# norbi_lm_main.net
KiCad netlist of a schematic drawn in Altium Designer
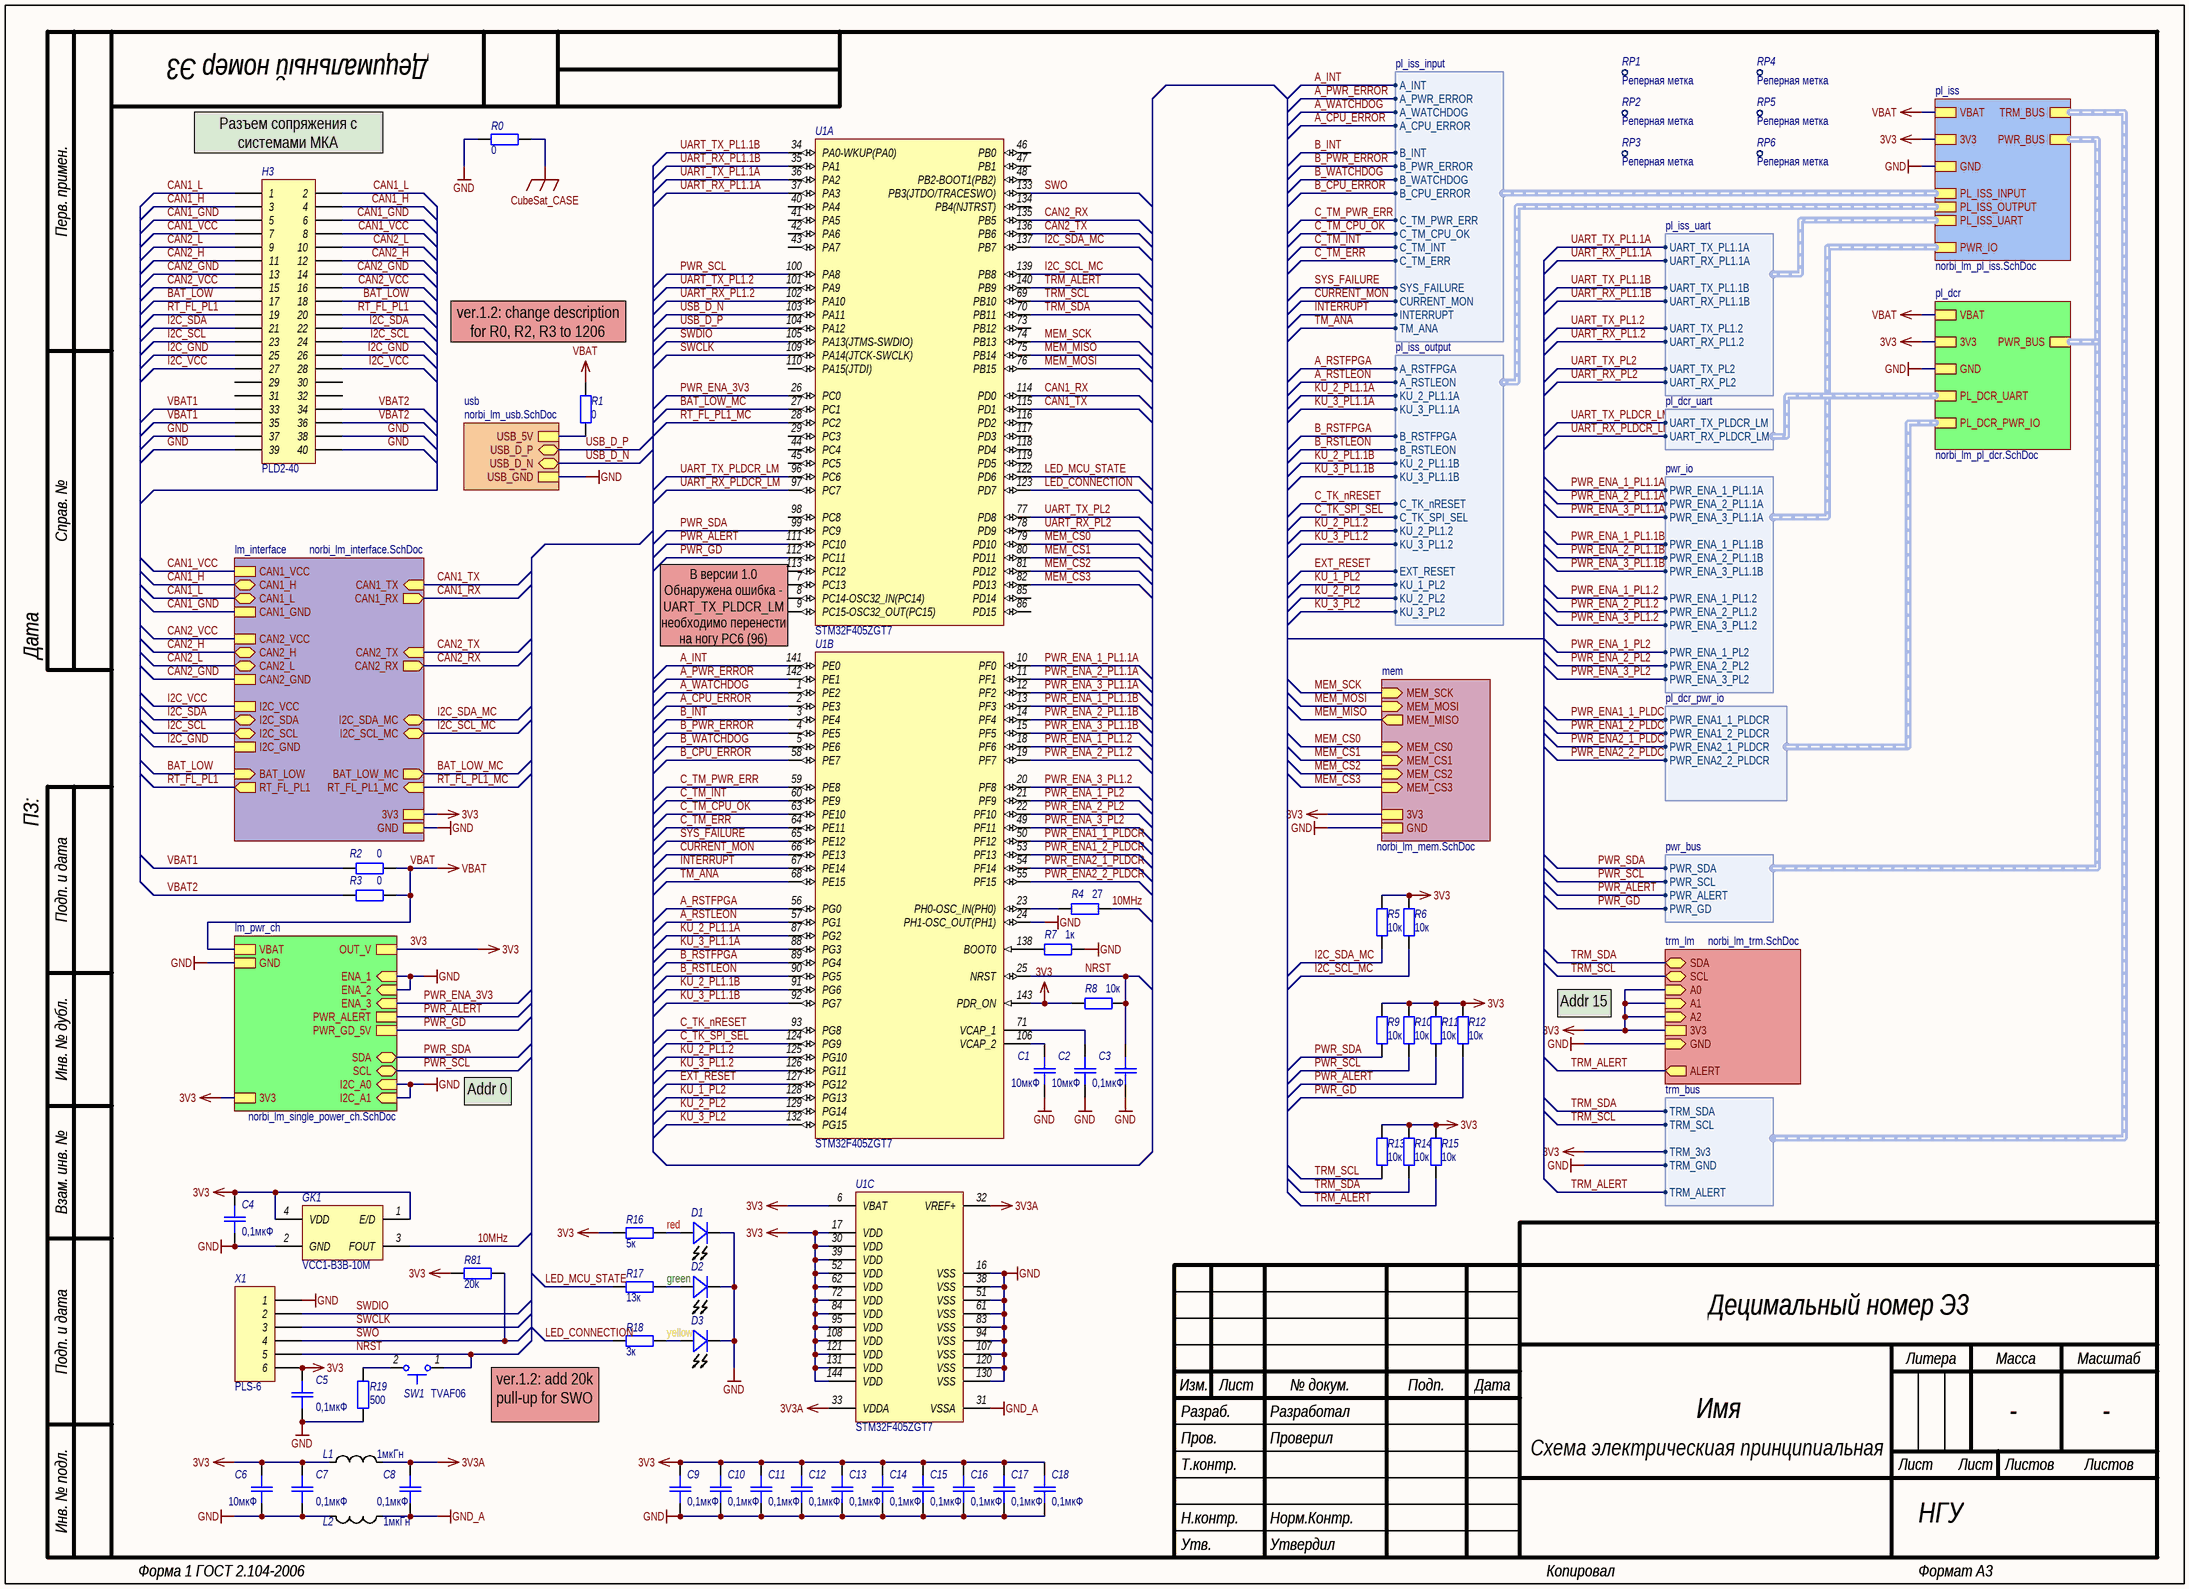
[diagram p0: norbi_lm_main.SchDoc]

(export (version "E")
  (design (tool "Eeschema 10.0.6"))
  (components
    (comp (ref "C1")
      (value "10мкФ")
      (footprint "CR-0603")
      (description "Конденсатор для поверхностного монтажа")
      (libsource (lib "my_passive") (part "C_smd"))
    )
    (comp (ref "C2")
      (value "10мкФ")
      (footprint "CR-0603")
      (description "Конденсатор для поверхностного монтажа")
      (libsource (lib "my_passive") (part "C_smd"))
    )
    (comp (ref "C3")
      (value "0,1мкФ")
      (footprint "CR-0603")
      (description "Конденсатор для поверхностного монтажа")
      (libsource (lib "my_passive") (part "C_smd"))
    )
    (comp (ref "C4")
      (value "0,1мкФ")
      (footprint "CR-0603")
      (description "Конденсатор для поверхностного монтажа")
      (libsource (lib "my_passive") (part "C_smd"))
    )
    (comp (ref "C5")
      (value "0,1мкФ")
      (footprint "CR-0603")
      (description "Конденсатор для поверхностного монтажа")
      (libsource (lib "my_passive") (part "C_smd"))
    )
    (comp (ref "C6")
      (value "10мкФ")
      (footprint "CR-0603")
      (description "Конденсатор для поверхностного монтажа")
      (libsource (lib "my_passive") (part "C_smd"))
    )
    (comp (ref "C7")
      (value "0,1мкФ")
      (footprint "CR-0603")
      (description "Конденсатор для поверхностного монтажа")
      (libsource (lib "my_passive") (part "C_smd"))
    )
    (comp (ref "C8")
      (value "0,1мкФ")
      (footprint "CR-0603")
      (description "Конденсатор для поверхностного монтажа")
      (libsource (lib "my_passive") (part "C_smd"))
    )
    (comp (ref "C9")
      (value "0,1мкФ")
      (footprint "CR-0603")
      (description "Конденсатор для поверхностного монтажа")
      (libsource (lib "my_passive") (part "C_smd"))
    )
    (comp (ref "C10")
      (value "0,1мкФ")
      (footprint "CR-0603")
      (description "Конденсатор для поверхностного монтажа")
      (libsource (lib "my_passive") (part "C_smd"))
    )
    (comp (ref "C11")
      (value "0,1мкФ")
      (footprint "CR-0603")
      (description "Конденсатор для поверхностного монтажа")
      (libsource (lib "my_passive") (part "C_smd"))
    )
    (comp (ref "C12")
      (value "0,1мкФ")
      (footprint "CR-0603")
      (description "Конденсатор для поверхностного монтажа")
      (libsource (lib "my_passive") (part "C_smd"))
    )
    (comp (ref "C13")
      (value "0,1мкФ")
      (footprint "CR-0603")
      (description "Конденсатор для поверхностного монтажа")
      (libsource (lib "my_passive") (part "C_smd"))
    )
    (comp (ref "C14")
      (value "0,1мкФ")
      (footprint "CR-0603")
      (description "Конденсатор для поверхностного монтажа")
      (libsource (lib "my_passive") (part "C_smd"))
    )
    (comp (ref "C15")
      (value "0,1мкФ")
      (footprint "CR-0603")
      (description "Конденсатор для поверхностного монтажа")
      (libsource (lib "my_passive") (part "C_smd"))
    )
    (comp (ref "C16")
      (value "0,1мкФ")
      (footprint "CR-0603")
      (description "Конденсатор для поверхностного монтажа")
      (libsource (lib "my_passive") (part "C_smd"))
    )
    (comp (ref "C17")
      (value "0,1мкФ")
      (footprint "CR-0603")
      (description "Конденсатор для поверхностного монтажа")
      (libsource (lib "my_passive") (part "C_smd"))
    )
    (comp (ref "C18")
      (value "0,1мкФ")
      (footprint "CR-0603")
      (description "Конденсатор для поверхностного монтажа")
      (libsource (lib "my_passive") (part "C_smd"))
    )
    (comp (ref "D1")
      (value "red")
      (footprint "LED-0805")
      (fields (field (name "Comment") "LED"))
      (libsource (lib "my_semicond") (part "LED"))
    )
    (comp (ref "D2")
      (value "green")
      (footprint "LED-0805")
      (fields (field (name "Comment") "LED"))
      (libsource (lib "my_semicond") (part "LED"))
    )
    (comp (ref "D3")
      (value "yellow")
      (footprint "LED-0805")
      (fields (field (name "Comment") "LED"))
      (libsource (lib "my_semicond") (part "LED"))
    )
    (comp (ref "GK1")
      (value "VCC1")
      (footprint "5x7 Crystall Oscillatior")
      (fields (field (name "НАИМЕНОВАНИЕ") "VCC1-B3B-10M"))
      (libsource (lib "my_integrated_circuit") (part "Crystall Oscillator"))
    )
    (comp (ref "H3")
      (value "Header 20X2H")
      (footprint "PLD2-40 (DS-1025-05 2x20)")
      (description "Header, 20-Pin, Dual row, Right Angle")
      (fields (field (name "НАИМЕНОВАНИЕ") "PLD2-40"))
      (libsource (lib "my_connector") (part "HDR2X20"))
    )
    (comp (ref "L1")
      (value "1мкГн")
      (footprint "CR-0805")
      (description "Индуктивность для поверхностнгого монтажа")
      (libsource (lib "my_passive") (part "L_smd"))
    )
    (comp (ref "L2")
      (value "1мкГн")
      (footprint "CR-0805")
      (description "Индуктивность для поверхностнгого монтажа")
      (libsource (lib "my_passive") (part "L_smd"))
    )
    (comp (ref "R0")
      (value "0")
      (footprint "CR-0805")
      (description "Резистор для поверхностного монтажа")
      (libsource (lib "") (part "R_smd_3"))
    )
    (comp (ref "R1")
      (value "0")
      (footprint "CR-1206")
      (description "Резистор для поверхностного монтажа")
      (libsource (lib "") (part "R_smd_2"))
    )
    (comp (ref "R2")
      (value "0")
      (footprint "CR-1206")
      (description "Резистор для поверхностного монтажа")
      (libsource (lib "my_passive") (part "R_smd"))
    )
    (comp (ref "R3")
      (value "0")
      (footprint "CR-1206")
      (description "Резистор для поверхностного монтажа")
      (libsource (lib "my_passive") (part "R_smd"))
    )
    (comp (ref "R4")
      (value "27")
      (footprint "CR-0603")
      (description "Резистор для поверхностного монтажа")
      (libsource (lib "my_passive") (part "R_smd"))
    )
    (comp (ref "R5")
      (value "10к")
      (footprint "CR-0603")
      (description "Резистор для поверхностного монтажа")
      (libsource (lib "") (part "R_smd_1"))
    )
    (comp (ref "R6")
      (value "10к")
      (footprint "CR-0603")
      (description "Резистор для поверхностного монтажа")
      (libsource (lib "") (part "R_smd_1"))
    )
    (comp (ref "R7")
      (value "1к")
      (footprint "CR-0603")
      (description "Резистор для поверхностного монтажа")
      (libsource (lib "") (part "R_smd_3"))
    )
    (comp (ref "R8")
      (value "10к")
      (footprint "CR-0603")
      (description "Резистор для поверхностного монтажа")
      (libsource (lib "") (part "R_smd_3"))
    )
    (comp (ref "R9")
      (value "10к")
      (footprint "CR-0603")
      (description "Резистор для поверхностного монтажа")
      (libsource (lib "") (part "R_smd_1"))
    )
    (comp (ref "R10")
      (value "10к")
      (footprint "CR-0603")
      (description "Резистор для поверхностного монтажа")
      (libsource (lib "") (part "R_smd_1"))
    )
    (comp (ref "R11")
      (value "10к")
      (footprint "CR-0603")
      (description "Резистор для поверхностного монтажа")
      (libsource (lib "") (part "R_smd_1"))
    )
    (comp (ref "R12")
      (value "10к")
      (footprint "CR-0603")
      (description "Резистор для поверхностного монтажа")
      (libsource (lib "") (part "R_smd_1"))
    )
    (comp (ref "R13")
      (value "10к")
      (footprint "CR-0603")
      (description "Резистор для поверхностного монтажа")
      (libsource (lib "") (part "R_smd_1"))
    )
    (comp (ref "R14")
      (value "10к")
      (footprint "CR-0603")
      (description "Резистор для поверхностного монтажа")
      (libsource (lib "") (part "R_smd_1"))
    )
    (comp (ref "R15")
      (value "10к")
      (footprint "CR-0603")
      (description "Резистор для поверхностного монтажа")
      (libsource (lib "") (part "R_smd_1"))
    )
    (comp (ref "R16")
      (value "5к")
      (footprint "CR-0603")
      (description "Резистор для поверхностного монтажа")
      (libsource (lib "") (part "R_smd_2"))
    )
    (comp (ref "R17")
      (value "13к")
      (footprint "CR-0603")
      (description "Резистор для поверхностного монтажа")
      (libsource (lib "") (part "R_smd_2"))
    )
    (comp (ref "R18")
      (value "3к")
      (footprint "CR-0603")
      (description "Резистор для поверхностного монтажа")
      (libsource (lib "") (part "R_smd_2"))
    )
    (comp (ref "R19")
      (value "500")
      (footprint "CR-0603")
      (description "Резистор для поверхностного монтажа")
      (libsource (lib "") (part "R_smd_1"))
    )
    (comp (ref "R81")
      (value "20k")
      (footprint "CR-0603")
      (description "Резистор для поверхностного монтажа")
      (libsource (lib "my_passive") (part "R_smd"))
    )
    (comp (ref "RP1")
      (value "RP")
      (footprint "ReperPoint")
      (fields (field (name "НАИМЕНОВАНИЕ") "Реперная метка"))
      (libsource (lib "Connector") (part "RP"))
    )
    (comp (ref "RP2")
      (value "RP")
      (footprint "ReperPoint")
      (fields (field (name "НАИМЕНОВАНИЕ") "Реперная метка"))
      (libsource (lib "Connector") (part "RP"))
    )
    (comp (ref "RP3")
      (value "RP")
      (footprint "ReperPoint")
      (fields (field (name "НАИМЕНОВАНИЕ") "Реперная метка"))
      (libsource (lib "Connector") (part "RP"))
    )
    (comp (ref "RP4")
      (value "RP")
      (footprint "ReperPoint")
      (fields (field (name "НАИМЕНОВАНИЕ") "Реперная метка"))
      (libsource (lib "Connector") (part "RP"))
    )
    (comp (ref "RP5")
      (value "RP")
      (footprint "ReperPoint")
      (fields (field (name "НАИМЕНОВАНИЕ") "Реперная метка"))
      (libsource (lib "Connector") (part "RP"))
    )
    (comp (ref "RP6")
      (value "RP")
      (footprint "ReperPoint")
      (fields (field (name "НАИМЕНОВАНИЕ") "Реперная метка"))
      (libsource (lib "Connector") (part "RP"))
    )
    (comp (ref "SW1")
      (value "Push button")
      (footprint "TVAF06")
      (fields (field (name "НАИМЕНОВАНИЕ") "TVAF06"))
      (libsource (lib "my_passive") (part "Push_Button"))
    )
    (comp (ref "U1")
      (value "STM32F405ZGT7")
      (footprint "LQFP144")
      (fields (field (name "НАИМЕНОВАНИЕ") "STM32F405ZGT7"))
      (libsource (lib "my_mcu") (part "STM32F405ZGT"))
    )
    (comp (ref "X1")
      (value "Header 6")
      (footprint "HDR1X6")
      (description "Header, 6-Pin")
      (fields (field (name "НАИМЕНОВАНИЕ") "PLS-6") (field (name "PUBLISHER") "Altium Limited"))
      (libsource (lib "Miscellaneous Connectors") (part "Header 6"))
    )
  )
  (nets
    (net (code "9") (name "/10MHz") (class "Default")
      (node (ref "GK1") (pin "3") (pinfunction "FOUT_3") (pintype "passive"))
      (node (ref "R4") (pin "2") (pinfunction "2_2") (pintype "passive"))
    )
    (net (code "10") (name "/A_CPU_ERROR") (class "Default")
      (node (ref "U1") (pin "2") (pinfunction "PE3_2") (pintype "bidirectional"))
    )
    (net (code "11") (name "/A_INT") (class "Default")
      (node (ref "U1") (pin "141") (pinfunction "PE0_141") (pintype "bidirectional"))
    )
    (net (code "12") (name "/A_PWR_ERROR") (class "Default")
      (node (ref "U1") (pin "142") (pinfunction "PE1_142") (pintype "bidirectional"))
    )
    (net (code "13") (name "/A_RSTFPGA") (class "Default")
      (node (ref "U1") (pin "56") (pinfunction "PG0_56") (pintype "bidirectional"))
    )
    (net (code "14") (name "/A_RSTLEON") (class "Default")
      (node (ref "U1") (pin "57") (pinfunction "PG1_57") (pintype "bidirectional"))
    )
    (net (code "15") (name "/A_WATCHDOG") (class "Default")
      (node (ref "U1") (pin "1") (pinfunction "PE2_1") (pintype "bidirectional"))
    )
    (net (code "16") (name "/BAT_LOW") (class "Default")
      (node (ref "H3") (pin "17") (pinfunction "17_17") (pintype "passive"))
      (node (ref "H3") (pin "18") (pinfunction "18_18") (pintype "passive"))
    )
    (net (code "17") (name "/BAT_LOW_MC") (class "Default")
      (node (ref "U1") (pin "27") (pinfunction "PC1_27") (pintype "bidirectional"))
    )
    (net (code "18") (name "/B_CPU_ERROR") (class "Default")
      (node (ref "U1") (pin "58") (pinfunction "PE7_58") (pintype "bidirectional"))
    )
    (net (code "19") (name "/B_INT") (class "Default")
      (node (ref "U1") (pin "3") (pinfunction "PE4_3") (pintype "bidirectional"))
    )
    (net (code "20") (name "/B_PWR_ERROR") (class "Default")
      (node (ref "U1") (pin "4") (pinfunction "PE5_4") (pintype "bidirectional"))
    )
    (net (code "21") (name "/B_RSTFPGA") (class "Default")
      (node (ref "U1") (pin "89") (pinfunction "PG4_89") (pintype "bidirectional"))
    )
    (net (code "22") (name "/B_RSTLEON") (class "Default")
      (node (ref "U1") (pin "90") (pinfunction "PG5_90") (pintype "bidirectional"))
    )
    (net (code "23") (name "/B_WATCHDOG") (class "Default")
      (node (ref "U1") (pin "5") (pinfunction "PE6_5") (pintype "bidirectional"))
    )
    (net (code "24") (name "/CAN1_GND") (class "Default")
      (node (ref "H3") (pin "5") (pinfunction "5_5") (pintype "passive"))
      (node (ref "H3") (pin "6") (pinfunction "6_6") (pintype "passive"))
    )
    (net (code "25") (name "/CAN1_H") (class "Default")
      (node (ref "H3") (pin "3") (pinfunction "3_3") (pintype "passive"))
      (node (ref "H3") (pin "4") (pinfunction "4_4") (pintype "passive"))
    )
    (net (code "26") (name "/CAN1_L") (class "Default")
      (node (ref "H3") (pin "1") (pinfunction "1_1") (pintype "passive"))
      (node (ref "H3") (pin "2") (pinfunction "2_2") (pintype "passive"))
    )
    (net (code "27") (name "/CAN1_RX") (class "Default")
      (node (ref "U1") (pin "114") (pinfunction "PD0_114") (pintype "bidirectional"))
    )
    (net (code "28") (name "/CAN1_TX") (class "Default")
      (node (ref "U1") (pin "115") (pinfunction "PD1_115") (pintype "bidirectional"))
    )
    (net (code "29") (name "/CAN1_VCC") (class "Default")
      (node (ref "H3") (pin "7") (pinfunction "7_7") (pintype "passive"))
      (node (ref "H3") (pin "8") (pinfunction "8_8") (pintype "passive"))
    )
    (net (code "30") (name "/CAN2_GND") (class "Default")
      (node (ref "H3") (pin "13") (pinfunction "13_13") (pintype "passive"))
      (node (ref "H3") (pin "14") (pinfunction "14_14") (pintype "passive"))
    )
    (net (code "31") (name "/CAN2_H") (class "Default")
      (node (ref "H3") (pin "11") (pinfunction "11_11") (pintype "passive"))
      (node (ref "H3") (pin "12") (pinfunction "12_12") (pintype "passive"))
    )
    (net (code "32") (name "/CAN2_L") (class "Default")
      (node (ref "H3") (pin "10") (pinfunction "10_10") (pintype "passive"))
      (node (ref "H3") (pin "9") (pinfunction "9_9") (pintype "passive"))
    )
    (net (code "33") (name "/CAN2_RX") (class "Default")
      (node (ref "U1") (pin "135") (pinfunction "PB5_135") (pintype "bidirectional"))
    )
    (net (code "34") (name "/CAN2_TX") (class "Default")
      (node (ref "U1") (pin "136") (pinfunction "PB6_136") (pintype "bidirectional"))
    )
    (net (code "35") (name "/CAN2_VCC") (class "Default")
      (node (ref "H3") (pin "15") (pinfunction "15_15") (pintype "passive"))
      (node (ref "H3") (pin "16") (pinfunction "16_16") (pintype "passive"))
    )
    (net (code "36") (name "/CURRENT_MON") (class "Default")
      (node (ref "U1") (pin "66") (pinfunction "PE13_66") (pintype "bidirectional"))
    )
    (net (code "37") (name "/C_TK_SPI_SEL") (class "Default")
      (node (ref "U1") (pin "124") (pinfunction "PG9_124") (pintype "bidirectional"))
    )
    (net (code "38") (name "/C_TK_nRESET") (class "Default")
      (node (ref "U1") (pin "93") (pinfunction "PG8_93") (pintype "bidirectional"))
    )
    (net (code "39") (name "/C_TM_CPU_OK") (class "Default")
      (node (ref "U1") (pin "63") (pinfunction "PE10_63") (pintype "bidirectional"))
    )
    (net (code "40") (name "/C_TM_ERR") (class "Default")
      (node (ref "U1") (pin "64") (pinfunction "PE11_64") (pintype "bidirectional"))
    )
    (net (code "41") (name "/C_TM_INT") (class "Default")
      (node (ref "U1") (pin "60") (pinfunction "PE9_60") (pintype "bidirectional"))
    )
    (net (code "42") (name "/C_TM_PWR_ERR") (class "Default")
      (node (ref "U1") (pin "59") (pinfunction "PE8_59") (pintype "bidirectional"))
    )
    (net (code "43") (name "/EXT_RESET") (class "Default")
      (node (ref "U1") (pin "127") (pinfunction "PG12_127") (pintype "bidirectional"))
    )
    (net (code "44") (name "/I2C_GND") (class "Default")
      (node (ref "H3") (pin "25") (pinfunction "25_25") (pintype "passive"))
      (node (ref "H3") (pin "26") (pinfunction "26_26") (pintype "passive"))
    )
    (net (code "45") (name "/I2C_SCL") (class "Default")
      (node (ref "H3") (pin "23") (pinfunction "23_23") (pintype "passive"))
      (node (ref "H3") (pin "24") (pinfunction "24_24") (pintype "passive"))
    )
    (net (code "46") (name "/I2C_SCL_MC") (class "Default")
      (node (ref "R6") (pin "2") (pinfunction "2_2") (pintype "passive"))
      (node (ref "U1") (pin "139") (pinfunction "PB8_139") (pintype "bidirectional"))
    )
    (net (code "47") (name "/I2C_SDA") (class "Default")
      (node (ref "H3") (pin "21") (pinfunction "21_21") (pintype "passive"))
      (node (ref "H3") (pin "22") (pinfunction "22_22") (pintype "passive"))
    )
    (net (code "48") (name "/I2C_SDA_MC") (class "Default")
      (node (ref "R5") (pin "2") (pinfunction "2_2") (pintype "passive"))
      (node (ref "U1") (pin "137") (pinfunction "PB7_137") (pintype "bidirectional"))
    )
    (net (code "49") (name "/I2C_VCC") (class "Default")
      (node (ref "H3") (pin "27") (pinfunction "27_27") (pintype "passive"))
      (node (ref "H3") (pin "28") (pinfunction "28_28") (pintype "passive"))
    )
    (net (code "50") (name "/INTERRUPT") (class "Default")
      (node (ref "U1") (pin "67") (pinfunction "PE14_67") (pintype "bidirectional"))
    )
    (net (code "51") (name "/KU_1_PL2") (class "Default")
      (node (ref "U1") (pin "128") (pinfunction "PG13_128") (pintype "bidirectional"))
    )
    (net (code "52") (name "/KU_2_PL1.1A") (class "Default")
      (node (ref "U1") (pin "87") (pinfunction "PG2_87") (pintype "bidirectional"))
    )
    (net (code "53") (name "/KU_2_PL1.1B") (class "Default")
      (node (ref "U1") (pin "91") (pinfunction "PG6_91") (pintype "bidirectional"))
    )
    (net (code "54") (name "/KU_2_PL1.2") (class "Default")
      (node (ref "U1") (pin "125") (pinfunction "PG10_125") (pintype "bidirectional"))
    )
    (net (code "55") (name "/KU_2_PL2") (class "Default")
      (node (ref "U1") (pin "129") (pinfunction "PG14_129") (pintype "bidirectional"))
    )
    (net (code "56") (name "/KU_3_PL1.1A") (class "Default")
      (node (ref "U1") (pin "88") (pinfunction "PG3_88") (pintype "bidirectional"))
    )
    (net (code "57") (name "/KU_3_PL1.1B") (class "Default")
      (node (ref "U1") (pin "92") (pinfunction "PG7_92") (pintype "bidirectional"))
    )
    (net (code "58") (name "/KU_3_PL1.2") (class "Default")
      (node (ref "U1") (pin "126") (pinfunction "PG11_126") (pintype "bidirectional"))
    )
    (net (code "59") (name "/KU_3_PL2") (class "Default")
      (node (ref "U1") (pin "132") (pinfunction "PG15_132") (pintype "bidirectional"))
    )
    (net (code "60") (name "/LED_CONNECTION") (class "Default")
      (node (ref "R18") (pin "1") (pinfunction "1_1") (pintype "passive"))
      (node (ref "U1") (pin "123") (pinfunction "PD7_123") (pintype "bidirectional"))
    )
    (net (code "61") (name "/LED_MCU_STATE") (class "Default")
      (node (ref "R17") (pin "1") (pinfunction "1_1") (pintype "passive"))
      (node (ref "U1") (pin "122") (pinfunction "PD6_122") (pintype "bidirectional"))
    )
    (net (code "62") (name "/MEM_CS0") (class "Default")
      (node (ref "U1") (pin "79") (pinfunction "PD10_79") (pintype "bidirectional"))
    )
    (net (code "63") (name "/MEM_CS1") (class "Default")
      (node (ref "U1") (pin "80") (pinfunction "PD11_80") (pintype "bidirectional"))
    )
    (net (code "64") (name "/MEM_CS2") (class "Default")
      (node (ref "U1") (pin "81") (pinfunction "PD12_81") (pintype "bidirectional"))
    )
    (net (code "65") (name "/MEM_CS3") (class "Default")
      (node (ref "U1") (pin "82") (pinfunction "PD13_82") (pintype "bidirectional"))
    )
    (net (code "66") (name "/MEM_MISO") (class "Default")
      (node (ref "U1") (pin "75") (pinfunction "PB14_75") (pintype "bidirectional"))
    )
    (net (code "67") (name "/MEM_MOSI") (class "Default")
      (node (ref "U1") (pin "76") (pinfunction "PB15_76") (pintype "bidirectional"))
    )
    (net (code "68") (name "/MEM_SCK") (class "Default")
      (node (ref "U1") (pin "74") (pinfunction "PB13_74") (pintype "bidirectional"))
    )
    (net (code "69") (name "/NRST") (class "Default")
      (node (ref "C3") (pin "2") (pinfunction "2_2") (pintype "passive"))
      (node (ref "R8") (pin "1") (pinfunction "1_1") (pintype "passive"))
      (node (ref "SW1") (pin "1") (pinfunction "1_1") (pintype "passive"))
      (node (ref "U1") (pin "25") (pinfunction "NRST_25") (pintype "bidirectional"))
      (node (ref "X1") (pin "5") (pinfunction "5_5") (pintype "passive"))
    )
    (net (code "70") (name "/PWR_ALERT") (class "Default")
      (node (ref "R11") (pin "2") (pinfunction "2_2") (pintype "passive"))
      (node (ref "U1") (pin "111") (pinfunction "PC10_111") (pintype "bidirectional"))
    )
    (net (code "71") (name "/PWR_ENA1_1_PLDCR") (class "Default")
      (node (ref "U1") (pin "50") (pinfunction "PF12_50") (pintype "bidirectional"))
    )
    (net (code "72") (name "/PWR_ENA1_2_PLDCR") (class "Default")
      (node (ref "U1") (pin "53") (pinfunction "PF13_53") (pintype "bidirectional"))
    )
    (net (code "73") (name "/PWR_ENA2_1_PLDCR") (class "Default")
      (node (ref "U1") (pin "54") (pinfunction "PF14_54") (pintype "bidirectional"))
    )
    (net (code "74") (name "/PWR_ENA2_2_PLDCR") (class "Default")
      (node (ref "U1") (pin "55") (pinfunction "PF15_55") (pintype "bidirectional"))
    )
    (net (code "75") (name "/PWR_ENA_1_PL1.1A") (class "Default")
      (node (ref "U1") (pin "10") (pinfunction "PF0_10") (pintype "bidirectional"))
    )
    (net (code "76") (name "/PWR_ENA_1_PL1.1B") (class "Default")
      (node (ref "U1") (pin "13") (pinfunction "PF3_13") (pintype "bidirectional"))
    )
    (net (code "77") (name "/PWR_ENA_1_PL1.2") (class "Default")
      (node (ref "U1") (pin "18") (pinfunction "PF6_18") (pintype "bidirectional"))
    )
    (net (code "78") (name "/PWR_ENA_1_PL2") (class "Default")
      (node (ref "U1") (pin "21") (pinfunction "PF9_21") (pintype "bidirectional"))
    )
    (net (code "79") (name "/PWR_ENA_2_PL1.1A") (class "Default")
      (node (ref "U1") (pin "11") (pinfunction "PF1_11") (pintype "bidirectional"))
    )
    (net (code "80") (name "/PWR_ENA_2_PL1.1B") (class "Default")
      (node (ref "U1") (pin "14") (pinfunction "PF4_14") (pintype "bidirectional"))
    )
    (net (code "81") (name "/PWR_ENA_2_PL1.2") (class "Default")
      (node (ref "U1") (pin "19") (pinfunction "PF7_19") (pintype "bidirectional"))
    )
    (net (code "82") (name "/PWR_ENA_2_PL2") (class "Default")
      (node (ref "U1") (pin "22") (pinfunction "PF10_22") (pintype "bidirectional"))
    )
    (net (code "83") (name "/PWR_ENA_3V3") (class "Default")
      (node (ref "U1") (pin "26") (pinfunction "PC0_26") (pintype "bidirectional"))
    )
    (net (code "84") (name "/PWR_ENA_3_PL1.1A") (class "Default")
      (node (ref "U1") (pin "12") (pinfunction "PF2_12") (pintype "bidirectional"))
    )
    (net (code "85") (name "/PWR_ENA_3_PL1.1B") (class "Default")
      (node (ref "U1") (pin "15") (pinfunction "PF5_15") (pintype "bidirectional"))
    )
    (net (code "86") (name "/PWR_ENA_3_PL1.2") (class "Default")
      (node (ref "U1") (pin "20") (pinfunction "PF8_20") (pintype "bidirectional"))
    )
    (net (code "87") (name "/PWR_ENA_3_PL2") (class "Default")
      (node (ref "U1") (pin "49") (pinfunction "PF11_49") (pintype "bidirectional"))
    )
    (net (code "88") (name "/PWR_GD") (class "Default")
      (node (ref "R12") (pin "2") (pinfunction "2_2") (pintype "passive"))
      (node (ref "U1") (pin "112") (pinfunction "PC11_112") (pintype "bidirectional"))
    )
    (net (code "89") (name "/PWR_SCL") (class "Default")
      (node (ref "R10") (pin "2") (pinfunction "2_2") (pintype "passive"))
      (node (ref "U1") (pin "100") (pinfunction "PA8_100") (pintype "bidirectional"))
    )
    (net (code "90") (name "/PWR_SDA") (class "Default")
      (node (ref "R9") (pin "2") (pinfunction "2_2") (pintype "passive"))
      (node (ref "U1") (pin "99") (pinfunction "PC9_99") (pintype "bidirectional"))
    )
    (net (code "91") (name "/RT_FL_PL1") (class "Default")
      (node (ref "H3") (pin "19") (pinfunction "19_19") (pintype "passive"))
      (node (ref "H3") (pin "20") (pinfunction "20_20") (pintype "passive"))
    )
    (net (code "92") (name "/RT_FL_PL1_MC") (class "Default")
      (node (ref "U1") (pin "28") (pinfunction "PC2_28") (pintype "bidirectional"))
    )
    (net (code "93") (name "/SWCLK") (class "Default")
      (node (ref "U1") (pin "109") (pinfunction "PA14(JTCK-SWCLK)_109") (pintype "bidirectional"))
      (node (ref "X1") (pin "3") (pinfunction "3_3") (pintype "passive"))
    )
    (net (code "94") (name "/SWDIO") (class "Default")
      (node (ref "U1") (pin "105") (pinfunction "PA13(JTMS-SWDIO)_105") (pintype "bidirectional"))
      (node (ref "X1") (pin "2") (pinfunction "2_2") (pintype "passive"))
    )
    (net (code "95") (name "/SWO") (class "Default")
      (node (ref "R81") (pin "2") (pinfunction "2_2") (pintype "passive"))
      (node (ref "U1") (pin "133") (pinfunction "PB3(JTDO/TRACESWO)_133") (pintype "bidirectional"))
      (node (ref "X1") (pin "4") (pinfunction "4_4") (pintype "passive"))
    )
    (net (code "96") (name "/SYS_FAILURE") (class "Default")
      (node (ref "U1") (pin "65") (pinfunction "PE12_65") (pintype "bidirectional"))
    )
    (net (code "97") (name "/TM_ANA") (class "Default")
      (node (ref "U1") (pin "68") (pinfunction "PE15_68") (pintype "bidirectional"))
    )
    (net (code "98") (name "/TRM_ALERT") (class "Default")
      (node (ref "R15") (pin "2") (pinfunction "2_2") (pintype "passive"))
      (node (ref "U1") (pin "140") (pinfunction "PB9_140") (pintype "bidirectional"))
    )
    (net (code "99") (name "/TRM_SCL") (class "Default")
      (node (ref "R13") (pin "2") (pinfunction "2_2") (pintype "passive"))
      (node (ref "U1") (pin "69") (pinfunction "PB10_69") (pintype "bidirectional"))
    )
    (net (code "100") (name "/TRM_SDA") (class "Default")
      (node (ref "R14") (pin "2") (pinfunction "2_2") (pintype "passive"))
      (node (ref "U1") (pin "70") (pinfunction "PB11_70") (pintype "bidirectional"))
    )
    (net (code "101") (name "/UART_RX_PL1.1A") (class "Default")
      (node (ref "U1") (pin "37") (pinfunction "PA3_37") (pintype "bidirectional"))
    )
    (net (code "102") (name "/UART_RX_PL1.1B") (class "Default")
      (node (ref "U1") (pin "35") (pinfunction "PA1_35") (pintype "bidirectional"))
    )
    (net (code "103") (name "/UART_RX_PL1.2") (class "Default")
      (node (ref "U1") (pin "102") (pinfunction "PA10_102") (pintype "bidirectional"))
    )
    (net (code "104") (name "/UART_RX_PL2") (class "Default")
      (node (ref "U1") (pin "78") (pinfunction "PD9_78") (pintype "bidirectional"))
    )
    (net (code "105") (name "/UART_RX_PLDCR_LM") (class "Default")
      (node (ref "U1") (pin "97") (pinfunction "PC7_97") (pintype "bidirectional"))
    )
    (net (code "106") (name "/UART_TX_PL1.1A") (class "Default")
      (node (ref "U1") (pin "36") (pinfunction "PA2_36") (pintype "bidirectional"))
    )
    (net (code "107") (name "/UART_TX_PL1.1B") (class "Default")
      (node (ref "U1") (pin "34") (pinfunction "PA0-WKUP(PA0)_34") (pintype "bidirectional"))
    )
    (net (code "108") (name "/UART_TX_PL1.2") (class "Default")
      (node (ref "U1") (pin "101") (pinfunction "PA9_101") (pintype "bidirectional"))
    )
    (net (code "109") (name "/UART_TX_PL2") (class "Default")
      (node (ref "U1") (pin "77") (pinfunction "PD8_77") (pintype "bidirectional"))
    )
    (net (code "110") (name "/UART_TX_PLDCR_LM") (class "Default")
      (node (ref "U1") (pin "96") (pinfunction "PC6_96") (pintype "bidirectional"))
    )
    (net (code "111") (name "/USB_5V") (class "Default")
      (node (ref "R1") (pin "1") (pinfunction "1_1") (pintype "passive"))
    )
    (net (code "112") (name "/USB_D_N") (class "Default")
      (node (ref "U1") (pin "103") (pinfunction "PA11_103") (pintype "bidirectional"))
    )
    (net (code "113") (name "/USB_D_P") (class "Default")
      (node (ref "U1") (pin "104") (pinfunction "PA12_104") (pintype "bidirectional"))
    )
    (net (code "114") (name "/VBAT1") (class "Default")
      (node (ref "H3") (pin "33") (pinfunction "33_33") (pintype "passive"))
      (node (ref "H3") (pin "35") (pinfunction "35_35") (pintype "passive"))
      (node (ref "R2") (pin "1") (pinfunction "1_1") (pintype "passive"))
    )
    (net (code "115") (name "/VBAT2") (class "Default")
      (node (ref "H3") (pin "34") (pinfunction "34_34") (pintype "passive"))
      (node (ref "H3") (pin "36") (pinfunction "36_36") (pintype "passive"))
      (node (ref "R3") (pin "1") (pinfunction "1_1") (pintype "passive"))
    )
    (net (code "124") (name "3V3") (class "Default")
      (node (ref "C10") (pin "2") (pinfunction "2_2") (pintype "passive"))
      (node (ref "C11") (pin "2") (pinfunction "2_2") (pintype "passive"))
      (node (ref "C12") (pin "2") (pinfunction "2_2") (pintype "passive"))
      (node (ref "C13") (pin "2") (pinfunction "2_2") (pintype "passive"))
      (node (ref "C14") (pin "2") (pinfunction "2_2") (pintype "passive"))
      (node (ref "C15") (pin "2") (pinfunction "2_2") (pintype "passive"))
      (node (ref "C16") (pin "2") (pinfunction "2_2") (pintype "passive"))
      (node (ref "C17") (pin "2") (pinfunction "2_2") (pintype "passive"))
      (node (ref "C18") (pin "2") (pinfunction "2_2") (pintype "passive"))
      (node (ref "C4") (pin "2") (pinfunction "2_2") (pintype "passive"))
      (node (ref "C5") (pin "2") (pinfunction "2_2") (pintype "passive"))
      (node (ref "C6") (pin "2") (pinfunction "2_2") (pintype "passive"))
      (node (ref "C7") (pin "2") (pinfunction "2_2") (pintype "passive"))
      (node (ref "C9") (pin "2") (pinfunction "2_2") (pintype "passive"))
      (node (ref "GK1") (pin "1") (pinfunction "E/D_1") (pintype "passive"))
      (node (ref "GK1") (pin "4") (pinfunction "VDD_4") (pintype "passive"))
      (node (ref "L1") (pin "1") (pinfunction "1_1") (pintype "passive"))
      (node (ref "R10") (pin "1") (pinfunction "1_1") (pintype "passive"))
      (node (ref "R11") (pin "1") (pinfunction "1_1") (pintype "passive"))
      (node (ref "R12") (pin "1") (pinfunction "1_1") (pintype "passive"))
      (node (ref "R13") (pin "1") (pinfunction "1_1") (pintype "passive"))
      (node (ref "R14") (pin "1") (pinfunction "1_1") (pintype "passive"))
      (node (ref "R15") (pin "1") (pinfunction "1_1") (pintype "passive"))
      (node (ref "R16") (pin "1") (pinfunction "1_1") (pintype "passive"))
      (node (ref "R5") (pin "1") (pinfunction "1_1") (pintype "passive"))
      (node (ref "R6") (pin "1") (pinfunction "1_1") (pintype "passive"))
      (node (ref "R8") (pin "2") (pinfunction "2_2") (pintype "passive"))
      (node (ref "R81") (pin "1") (pinfunction "1_1") (pintype "passive"))
      (node (ref "R9") (pin "1") (pinfunction "1_1") (pintype "passive"))
      (node (ref "U1") (pin "108") (pinfunction "VDD_108") (pintype "power_in"))
      (node (ref "U1") (pin "121") (pinfunction "VDD_121") (pintype "power_in"))
      (node (ref "U1") (pin "131") (pinfunction "VDD_131") (pintype "power_in"))
      (node (ref "U1") (pin "143") (pinfunction "PDR_ON_143") (pintype "input"))
      (node (ref "U1") (pin "144") (pinfunction "VDD_144") (pintype "power_in"))
      (node (ref "U1") (pin "17") (pinfunction "VDD_17") (pintype "power_in"))
      (node (ref "U1") (pin "30") (pinfunction "VDD_30") (pintype "power_in"))
      (node (ref "U1") (pin "39") (pinfunction "VDD_39") (pintype "power_in"))
      (node (ref "U1") (pin "52") (pinfunction "VDD_52") (pintype "power_in"))
      (node (ref "U1") (pin "6") (pinfunction "VBAT_6") (pintype "power_in"))
      (node (ref "U1") (pin "62") (pinfunction "VDD_62") (pintype "power_in"))
      (node (ref "U1") (pin "72") (pinfunction "VDD_72") (pintype "power_in"))
      (node (ref "U1") (pin "84") (pinfunction "VDD_84") (pintype "power_in"))
      (node (ref "U1") (pin "95") (pinfunction "VDD_95") (pintype "power_in"))
      (node (ref "X1") (pin "6") (pinfunction "6_6") (pintype "passive"))
    )
    (net (code "125") (name "3V3A") (class "Default")
      (node (ref "C8") (pin "2") (pinfunction "2_2") (pintype "passive"))
      (node (ref "L1") (pin "2") (pinfunction "2_2") (pintype "passive"))
      (node (ref "U1") (pin "32") (pinfunction "VREF+_32") (pintype "power_in"))
      (node (ref "U1") (pin "33") (pinfunction "VDDA_33") (pintype "power_in"))
    )
    (net (code "126") (name "CubeSat_CASE") (class "Default")
      (node (ref "R0") (pin "1") (pinfunction "1_1") (pintype "passive"))
    )
    (net (code "127") (name "GND") (class "Default")
      (node (ref "C1") (pin "1") (pinfunction "1_1") (pintype "passive"))
      (node (ref "C10") (pin "1") (pinfunction "1_1") (pintype "passive"))
      (node (ref "C11") (pin "1") (pinfunction "1_1") (pintype "passive"))
      (node (ref "C12") (pin "1") (pinfunction "1_1") (pintype "passive"))
      (node (ref "C13") (pin "1") (pinfunction "1_1") (pintype "passive"))
      (node (ref "C14") (pin "1") (pinfunction "1_1") (pintype "passive"))
      (node (ref "C15") (pin "1") (pinfunction "1_1") (pintype "passive"))
      (node (ref "C16") (pin "1") (pinfunction "1_1") (pintype "passive"))
      (node (ref "C17") (pin "1") (pinfunction "1_1") (pintype "passive"))
      (node (ref "C18") (pin "1") (pinfunction "1_1") (pintype "passive"))
      (node (ref "C2") (pin "1") (pinfunction "1_1") (pintype "passive"))
      (node (ref "C3") (pin "1") (pinfunction "1_1") (pintype "passive"))
      (node (ref "C4") (pin "1") (pinfunction "1_1") (pintype "passive"))
      (node (ref "C5") (pin "1") (pinfunction "1_1") (pintype "passive"))
      (node (ref "C6") (pin "1") (pinfunction "1_1") (pintype "passive"))
      (node (ref "C7") (pin "1") (pinfunction "1_1") (pintype "passive"))
      (node (ref "C9") (pin "1") (pinfunction "1_1") (pintype "passive"))
      (node (ref "D1") (pin "2") (pinfunction "K_2") (pintype "passive"))
      (node (ref "D2") (pin "2") (pinfunction "K_2") (pintype "passive"))
      (node (ref "D3") (pin "2") (pinfunction "K_2") (pintype "passive"))
      (node (ref "GK1") (pin "2") (pinfunction "GND_2") (pintype "passive"))
      (node (ref "H3") (pin "37") (pinfunction "37_37") (pintype "passive"))
      (node (ref "H3") (pin "38") (pinfunction "38_38") (pintype "passive"))
      (node (ref "H3") (pin "39") (pinfunction "39_39") (pintype "passive"))
      (node (ref "H3") (pin "40") (pinfunction "40_40") (pintype "passive"))
      (node (ref "L2") (pin "2") (pinfunction "2_2") (pintype "passive"))
      (node (ref "R0") (pin "2") (pinfunction "2_2") (pintype "passive"))
      (node (ref "R19") (pin "2") (pinfunction "2_2") (pintype "passive"))
      (node (ref "R7") (pin "1") (pinfunction "1_1") (pintype "passive"))
      (node (ref "U1") (pin "107") (pinfunction "VSS_107") (pintype "power_in"))
      (node (ref "U1") (pin "120") (pinfunction "VSS_120") (pintype "power_in"))
      (node (ref "U1") (pin "130") (pinfunction "VSS_130") (pintype "power_in"))
      (node (ref "U1") (pin "16") (pinfunction "VSS_16") (pintype "power_in"))
      (node (ref "U1") (pin "24") (pinfunction "PH1-OSC_OUT(PH1)_24") (pintype "bidirectional"))
      (node (ref "U1") (pin "38") (pinfunction "VSS_38") (pintype "power_in"))
      (node (ref "U1") (pin "51") (pinfunction "VSS_51") (pintype "power_in"))
      (node (ref "U1") (pin "61") (pinfunction "VSS_61") (pintype "power_in"))
      (node (ref "U1") (pin "83") (pinfunction "VSS_83") (pintype "power_in"))
      (node (ref "U1") (pin "94") (pinfunction "VSS_94") (pintype "power_in"))
      (node (ref "X1") (pin "1") (pinfunction "1_1") (pintype "passive"))
    )
    (net (code "128") (name "GND_A") (class "Default")
      (node (ref "C8") (pin "1") (pinfunction "1_1") (pintype "passive"))
      (node (ref "L2") (pin "1") (pinfunction "1_1") (pintype "passive"))
      (node (ref "U1") (pin "31") (pinfunction "VSSA_31") (pintype "power_in"))
    )
    (net (code "129") (name "Net-(D1-A)") (class "Default")
      (node (ref "D1") (pin "1") (pinfunction "A_1") (pintype "passive"))
      (node (ref "R16") (pin "2") (pinfunction "2_2") (pintype "passive"))
    )
    (net (code "130") (name "Net-(D2-A)") (class "Default")
      (node (ref "D2") (pin "1") (pinfunction "A_1") (pintype "passive"))
      (node (ref "R17") (pin "2") (pinfunction "2_2") (pintype "passive"))
    )
    (net (code "131") (name "Net-(D3-A)") (class "Default")
      (node (ref "D3") (pin "1") (pinfunction "A_1") (pintype "passive"))
      (node (ref "R18") (pin "2") (pinfunction "2_2") (pintype "passive"))
    )
    (net (code "132") (name "Net-(R19-Pad1)") (class "Default")
      (node (ref "R19") (pin "1") (pinfunction "1_1") (pintype "passive"))
      (node (ref "SW1") (pin "2") (pinfunction "2_2") (pintype "passive"))
    )
    (net (code "133") (name "Net-(U1B-BOOT0)") (class "Default")
      (node (ref "R7") (pin "2") (pinfunction "2_2") (pintype "passive"))
      (node (ref "U1") (pin "138") (pinfunction "BOOT0_138") (pintype "input"))
    )
    (net (code "134") (name "Net-(U1B-PH0-OSC_IN(PH0))") (class "Default")
      (node (ref "R4") (pin "1") (pinfunction "1_1") (pintype "passive"))
      (node (ref "U1") (pin "23") (pinfunction "PH0-OSC_IN(PH0)_23") (pintype "bidirectional"))
    )
    (net (code "135") (name "Net-(U1B-VCAP_1)") (class "Default")
      (node (ref "C2") (pin "2") (pinfunction "2_2") (pintype "passive"))
      (node (ref "U1") (pin "71") (pinfunction "VCAP_1_71") (pintype "power_in"))
    )
    (net (code "136") (name "Net-(U1B-VCAP_2)") (class "Default")
      (node (ref "C1") (pin "2") (pinfunction "2_2") (pintype "passive"))
      (node (ref "U1") (pin "106") (pinfunction "VCAP_2_106") (pintype "power_in"))
    )
    (net (code "137") (name "VBAT") (class "Default")
      (node (ref "R1") (pin "2") (pinfunction "2_2") (pintype "passive"))
      (node (ref "R2") (pin "2") (pinfunction "2_2") (pintype "passive"))
      (node (ref "R3") (pin "2") (pinfunction "2_2") (pintype "passive"))
    )
    (net (code "138") (name "unconnected-(H3-Pad29)") (class "Default")
      (node (ref "H3") (pin "29") (pinfunction "29_29") (pintype "passive"))
    )
    (net (code "139") (name "unconnected-(H3-Pad30)") (class "Default")
      (node (ref "H3") (pin "30") (pinfunction "30_30") (pintype "passive"))
    )
    (net (code "140") (name "unconnected-(H3-Pad31)") (class "Default")
      (node (ref "H3") (pin "31") (pinfunction "31_31") (pintype "passive"))
    )
    (net (code "141") (name "unconnected-(H3-Pad32)") (class "Default")
      (node (ref "H3") (pin "32") (pinfunction "32_32") (pintype "passive"))
    )
    (net (code "142") (name "unconnected-(U1A-PA4-Pad40)") (class "Default")
      (node (ref "U1") (pin "40") (pinfunction "PA4_40") (pintype "bidirectional"))
    )
    (net (code "143") (name "unconnected-(U1A-PA5-Pad41)") (class "Default")
      (node (ref "U1") (pin "41") (pinfunction "PA5_41") (pintype "bidirectional"))
    )
    (net (code "144") (name "unconnected-(U1A-PA6-Pad42)") (class "Default")
      (node (ref "U1") (pin "42") (pinfunction "PA6_42") (pintype "bidirectional"))
    )
    (net (code "145") (name "unconnected-(U1A-PA7-Pad43)") (class "Default")
      (node (ref "U1") (pin "43") (pinfunction "PA7_43") (pintype "bidirectional"))
    )
    (net (code "146") (name "unconnected-(U1A-PA15(JTDI)-Pad110)") (class "Default")
      (node (ref "U1") (pin "110") (pinfunction "PA15(JTDI)_110") (pintype "bidirectional"))
    )
    (net (code "147") (name "unconnected-(U1A-PB0-Pad46)") (class "Default")
      (node (ref "U1") (pin "46") (pinfunction "PB0_46") (pintype "bidirectional"))
    )
    (net (code "148") (name "unconnected-(U1A-PB1-Pad47)") (class "Default")
      (node (ref "U1") (pin "47") (pinfunction "PB1_47") (pintype "bidirectional"))
    )
    (net (code "149") (name "unconnected-(U1A-PB2-BOOT1(PB2)-Pad48)") (class "Default")
      (node (ref "U1") (pin "48") (pinfunction "PB2-BOOT1(PB2)_48") (pintype "bidirectional"))
    )
    (net (code "150") (name "unconnected-(U1A-PB4(NJTRST)-Pad134)") (class "Default")
      (node (ref "U1") (pin "134") (pinfunction "PB4(NJTRST)_134") (pintype "bidirectional"))
    )
    (net (code "151") (name "unconnected-(U1A-PB12-Pad73)") (class "Default")
      (node (ref "U1") (pin "73") (pinfunction "PB12_73") (pintype "bidirectional"))
    )
    (net (code "152") (name "unconnected-(U1A-PC3-Pad29)") (class "Default")
      (node (ref "U1") (pin "29") (pinfunction "PC3_29") (pintype "bidirectional"))
    )
    (net (code "153") (name "unconnected-(U1A-PC4-Pad44)") (class "Default")
      (node (ref "U1") (pin "44") (pinfunction "PC4_44") (pintype "bidirectional"))
    )
    (net (code "154") (name "unconnected-(U1A-PC5-Pad45)") (class "Default")
      (node (ref "U1") (pin "45") (pinfunction "PC5_45") (pintype "bidirectional"))
    )
    (net (code "155") (name "unconnected-(U1A-PC8-Pad98)") (class "Default")
      (node (ref "U1") (pin "98") (pinfunction "PC8_98") (pintype "bidirectional"))
    )
    (net (code "156") (name "unconnected-(U1A-PC12-Pad113)") (class "Default")
      (node (ref "U1") (pin "113") (pinfunction "PC12_113") (pintype "bidirectional"))
    )
    (net (code "157") (name "unconnected-(U1A-PC13-Pad7)") (class "Default")
      (node (ref "U1") (pin "7") (pinfunction "PC13_7") (pintype "bidirectional"))
    )
    (net (code "158") (name "unconnected-(U1A-PC14-OSC32_IN(PC14)-Pad8)") (class "Default")
      (node (ref "U1") (pin "8") (pinfunction "PC14-OSC32_IN(PC14)_8") (pintype "bidirectional"))
    )
    (net (code "159") (name "unconnected-(U1A-PC15-OSC32_OUT(PC15)-Pad9)") (class "Default")
      (node (ref "U1") (pin "9") (pinfunction "PC15-OSC32_OUT(PC15)_9") (pintype "bidirectional"))
    )
    (net (code "160") (name "unconnected-(U1A-PD2-Pad116)") (class "Default")
      (node (ref "U1") (pin "116") (pinfunction "PD2_116") (pintype "bidirectional"))
    )
    (net (code "161") (name "unconnected-(U1A-PD3-Pad117)") (class "Default")
      (node (ref "U1") (pin "117") (pinfunction "PD3_117") (pintype "bidirectional"))
    )
    (net (code "162") (name "unconnected-(U1A-PD4-Pad118)") (class "Default")
      (node (ref "U1") (pin "118") (pinfunction "PD4_118") (pintype "bidirectional"))
    )
    (net (code "163") (name "unconnected-(U1A-PD5-Pad119)") (class "Default")
      (node (ref "U1") (pin "119") (pinfunction "PD5_119") (pintype "bidirectional"))
    )
    (net (code "164") (name "unconnected-(U1A-PD14-Pad85)") (class "Default")
      (node (ref "U1") (pin "85") (pinfunction "PD14_85") (pintype "bidirectional"))
    )
    (net (code "165") (name "unconnected-(U1A-PD15-Pad86)") (class "Default")
      (node (ref "U1") (pin "86") (pinfunction "PD15_86") (pintype "bidirectional"))
    )
  )
)
